# voltage-selector-and-output.net
KiCad netlist of a schematic drawn in EAGLE
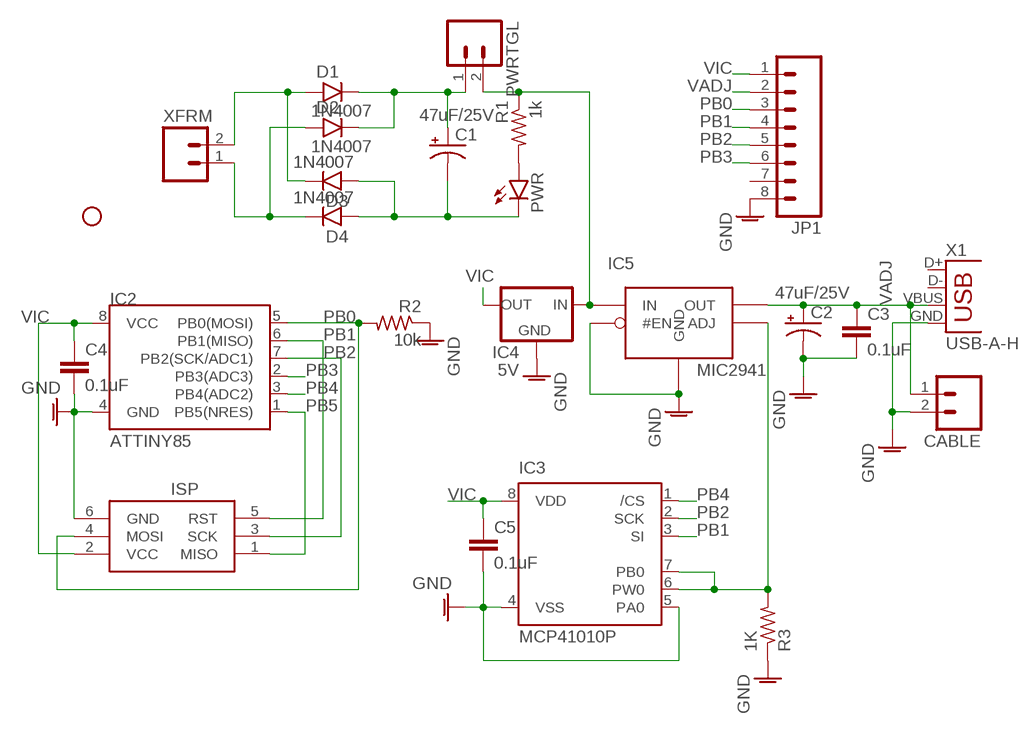
[diagram p0: schematic, sheet 1]

(export (version "E")
  (design (tool "Eeschema 10.0.6"))
  (components
    (comp (ref "C1")
      (value "47uF/25V")
      (footprint "eagle-import:E2,5-6")
      (libsource (lib "eagle-import") (part "CPOL-USE2.5-6"))
    )
    (comp (ref "C2")
      (value "47uF/25V")
      (footprint "eagle-import:E2,5-6")
      (libsource (lib "eagle-import") (part "CPOL-USE2.5-6"))
    )
    (comp (ref "C3")
      (value "0.1uF")
      (footprint "eagle-import:CAP-PTH-SMALL")
      (libsource (lib "eagle-import") (part "CAPPTH"))
    )
    (comp (ref "C4")
      (value "0.1uF")
      (footprint "eagle-import:CAP-PTH-SMALL")
      (libsource (lib "eagle-import") (part "CAPPTH"))
    )
    (comp (ref "C5")
      (value "0.1uF")
      (footprint "eagle-import:CAP-PTH-SMALL")
      (libsource (lib "eagle-import") (part "CAPPTH"))
    )
    (comp (ref "CABLE")
      (value "M02PTH")
      (footprint "eagle-import:1X02")
      (libsource (lib "eagle-import") (part "M02PTH"))
    )
    (comp (ref "D1")
      (value "1N4007")
      (footprint "eagle-import:DO41-3")
      (libsource (lib "eagle-import") (part "1N400X.3"))
    )
    (comp (ref "D2")
      (value "1N4007")
      (footprint "eagle-import:DO41-3")
      (libsource (lib "eagle-import") (part "1N400X.3"))
    )
    (comp (ref "D3")
      (value "1N4007")
      (footprint "eagle-import:DO41-3")
      (libsource (lib "eagle-import") (part "1N400X.3"))
    )
    (comp (ref "D4")
      (value "1N4007")
      (footprint "eagle-import:DO41-3")
      (libsource (lib "eagle-import") (part "1N400X.3"))
    )
    (comp (ref "IC2")
      (value "ATTINY85")
      (footprint "eagle-import:DIP08")
      (libsource (lib "eagle-import") (part "ATTINY13DIP"))
    )
    (comp (ref "IC3")
      (value "MCP41010P")
      (footprint "eagle-import:DIL8")
      (fields (field (name "MF") "MICROCHIP") (field (name "MPN") "MCP41010"))
      (libsource (lib "eagle-import") (part "MCP41010P"))
    )
    (comp (ref "IC4")
      (value "5V")
      (footprint "eagle-import:78XXS")
      (libsource (lib "eagle-import") (part "78XXS"))
    )
    (comp (ref "IC5")
      (value "MIC2941")
      (footprint "eagle-import:TO220-5")
      (libsource (lib "eagle-import") (part "MIC2941"))
    )
    (comp (ref "ISP")
      (value "AVRISP-6")
      (footprint "eagle-import:AVRISP")
      (libsource (lib "eagle-import") (part "AVRISP-6"))
    )
    (comp (ref "JP1")
      (value "M081X08")
      (footprint "eagle-import:1X08")
      (libsource (lib "eagle-import") (part "M081X08"))
    )
    (comp (ref "PWR")
      (value "LED-3MM-NO_SILK")
      (footprint "eagle-import:LED3MM-NS")
      (libsource (lib "eagle-import") (part "LED-3MM-NO_SILK"))
    )
    (comp (ref "PWRTGL")
      (value "M02PTH")
      (footprint "eagle-import:1X02")
      (libsource (lib "eagle-import") (part "M02PTH"))
    )
    (comp (ref "R1")
      (value "1k")
      (footprint "eagle-import:0207_5V")
      (libsource (lib "eagle-import") (part "R-US_0207/5V"))
    )
    (comp (ref "R2")
      (value "10k")
      (footprint "eagle-import:0207_5V")
      (libsource (lib "eagle-import") (part "R-US_0207/5V"))
    )
    (comp (ref "R3")
      (value "1K")
      (footprint "eagle-import:0207_5V")
      (libsource (lib "eagle-import") (part "R-US_0207/5V"))
    )
    (comp (ref "STANDOFF1")
      (value "STAND-OFF")
      (footprint "eagle-import:STAND-OFF")
      (libsource (lib "eagle-import") (part "STAND-OFF"))
    )
    (comp (ref "X1")
      (value "USB-A-H")
      (footprint "eagle-import:USB-A-H")
      (libsource (lib "eagle-import") (part "USB-A-H"))
    )
    (comp (ref "XFRM")
      (value "M02PTH")
      (footprint "eagle-import:1X02")
      (libsource (lib "eagle-import") (part "M02PTH"))
    )
  )
  (nets
    (net (code "1") (name "AGND") (class "Default")
      (node (ref "C2") (pin "-") (pinfunction "-_-") (pintype "passive"))
      (node (ref "C3") (pin "2") (pinfunction "2_2") (pintype "passive"))
      (node (ref "C4") (pin "2") (pinfunction "2_2") (pintype "passive"))
      (node (ref "C5") (pin "2") (pinfunction "2_2") (pintype "passive"))
      (node (ref "CABLE") (pin "2") (pinfunction "2_2") (pintype "passive"))
      (node (ref "IC2") (pin "4") (pinfunction "GND_4") (pintype "bidirectional"))
      (node (ref "IC3") (pin "4") (pinfunction "VSS_4") (pintype "power_in"))
      (node (ref "IC3") (pin "5") (pinfunction "PA0_5") (pintype "bidirectional"))
      (node (ref "IC4") (pin "GND") (pinfunction "GND_GND") (pintype "input"))
      (node (ref "IC5") (pin "2") (pinfunction "#EN_2") (pintype "input"))
      (node (ref "IC5") (pin "3") (pinfunction "GND_3") (pintype "input"))
      (node (ref "ISP") (pin "6") (pinfunction "GND_6") (pintype "power_in"))
      (node (ref "JP1") (pin "8") (pinfunction "8_8") (pintype "passive"))
      (node (ref "R2") (pin "1") (pinfunction "1_1") (pintype "passive"))
      (node (ref "R3") (pin "1") (pinfunction "1_1") (pintype "passive"))
      (node (ref "X1") (pin "GND") (pinfunction "GND_GND") (pintype "bidirectional"))
    )
    (net (code "2") (name "Net-(C1-Pad+)") (class "Default")
      (node (ref "C1") (pin "+") (pinfunction "+_+") (pintype "passive"))
      (node (ref "D1") (pin "C") (pinfunction "C_C") (pintype "passive"))
      (node (ref "D2") (pin "C") (pinfunction "C_C") (pintype "passive"))
      (node (ref "PWRTGL") (pin "1") (pinfunction "1_1") (pintype "passive"))
    )
    (net (code "3") (name "Net-(D1-PadA)") (class "Default")
      (node (ref "D1") (pin "A") (pinfunction "A_A") (pintype "passive"))
      (node (ref "D3") (pin "C") (pinfunction "C_C") (pintype "passive"))
      (node (ref "XFRM") (pin "2") (pinfunction "2_2") (pintype "passive"))
    )
    (net (code "4") (name "Net-(D2-PadA)") (class "Default")
      (node (ref "D2") (pin "A") (pinfunction "A_A") (pintype "passive"))
      (node (ref "D4") (pin "C") (pinfunction "C_C") (pintype "passive"))
      (node (ref "XFRM") (pin "1") (pinfunction "1_1") (pintype "passive"))
    )
    (net (code "5") (name "Net-(IC3-PB0)") (class "Default")
      (node (ref "IC3") (pin "6") (pinfunction "PW0_6") (pintype "bidirectional"))
      (node (ref "IC3") (pin "7") (pinfunction "PB0_7") (pintype "bidirectional"))
      (node (ref "IC5") (pin "1") (pinfunction "ADJ_1") (pintype "input"))
      (node (ref "R3") (pin "2") (pinfunction "2_2") (pintype "passive"))
    )
    (net (code "6") (name "Net-(IC5-IN)") (class "Default")
      (node (ref "IC4") (pin "IN") (pinfunction "IN_IN") (pintype "input"))
      (node (ref "IC5") (pin "4") (pinfunction "IN_4") (pintype "input"))
      (node (ref "PWRTGL") (pin "2") (pinfunction "2_2") (pintype "passive"))
      (node (ref "R1") (pin "1") (pinfunction "1_1") (pintype "passive"))
    )
    (net (code "7") (name "Net-(PWR-C)") (class "Default")
      (node (ref "C1") (pin "-") (pinfunction "-_-") (pintype "passive"))
      (node (ref "D3") (pin "A") (pinfunction "A_A") (pintype "passive"))
      (node (ref "D4") (pin "A") (pinfunction "A_A") (pintype "passive"))
      (node (ref "PWR") (pin "K") (pinfunction "C_K") (pintype "passive"))
    )
    (net (code "8") (name "Net-(PWR-PadA)") (class "Default")
      (node (ref "PWR") (pin "A") (pinfunction "A_A") (pintype "passive"))
      (node (ref "R1") (pin "2") (pinfunction "2_2") (pintype "passive"))
    )
    (net (code "9") (name "PB0") (class "Default")
      (node (ref "IC2") (pin "5") (pinfunction "PB0(MOSI)_5") (pintype "bidirectional"))
      (node (ref "ISP") (pin "4") (pinfunction "MOSI_4") (pintype "output"))
      (node (ref "JP1") (pin "3") (pinfunction "3_3") (pintype "passive"))
      (node (ref "R2") (pin "2") (pinfunction "2_2") (pintype "passive"))
    )
    (net (code "10") (name "PB1") (class "Default")
      (node (ref "IC2") (pin "6") (pinfunction "PB1(MISO)_6") (pintype "bidirectional"))
      (node (ref "IC3") (pin "3") (pinfunction "SI_3") (pintype "input"))
      (node (ref "ISP") (pin "5") (pinfunction "RST_5") (pintype "output"))
      (node (ref "JP1") (pin "4") (pinfunction "4_4") (pintype "passive"))
    )
    (net (code "11") (name "PB2") (class "Default")
      (node (ref "IC2") (pin "7") (pinfunction "PB2(SCK/ADC1)_7") (pintype "bidirectional"))
      (node (ref "IC3") (pin "2") (pinfunction "SCK_2") (pintype "input"))
      (node (ref "ISP") (pin "3") (pinfunction "SCK_3") (pintype "output"))
      (node (ref "JP1") (pin "5") (pinfunction "5_5") (pintype "passive"))
    )
    (net (code "12") (name "PB3") (class "Default")
      (node (ref "IC2") (pin "2") (pinfunction "PB3(ADC3)_2") (pintype "bidirectional"))
      (node (ref "JP1") (pin "6") (pinfunction "6_6") (pintype "passive"))
    )
    (net (code "13") (name "PB4") (class "Default")
      (node (ref "IC2") (pin "3") (pinfunction "PB4(ADC2)_3") (pintype "bidirectional"))
      (node (ref "IC3") (pin "1") (pinfunction "/CS_1") (pintype "input"))
    )
    (net (code "14") (name "PB5") (class "Default")
      (node (ref "IC2") (pin "1") (pinfunction "PB5(NRES)_1") (pintype "bidirectional"))
      (node (ref "ISP") (pin "1") (pinfunction "MISO_1") (pintype "input"))
    )
    (net (code "15") (name "VADJ") (class "Default")
      (node (ref "C2") (pin "+") (pinfunction "+_+") (pintype "passive"))
      (node (ref "C3") (pin "1") (pinfunction "1_1") (pintype "passive"))
      (node (ref "CABLE") (pin "1") (pinfunction "1_1") (pintype "passive"))
      (node (ref "IC5") (pin "5") (pinfunction "OUT_5") (pintype "passive"))
      (node (ref "JP1") (pin "2") (pinfunction "2_2") (pintype "passive"))
      (node (ref "X1") (pin "VBUS") (pinfunction "VBUS_VBUS") (pintype "bidirectional"))
    )
    (net (code "16") (name "VIC") (class "Default")
      (node (ref "C4") (pin "1") (pinfunction "1_1") (pintype "passive"))
      (node (ref "C5") (pin "1") (pinfunction "1_1") (pintype "passive"))
      (node (ref "IC2") (pin "8") (pinfunction "VCC_8") (pintype "bidirectional"))
      (node (ref "IC3") (pin "8") (pinfunction "VDD_8") (pintype "power_in"))
      (node (ref "IC4") (pin "OUT") (pinfunction "OUT_OUT") (pintype "passive"))
      (node (ref "ISP") (pin "2") (pinfunction "VCC_2") (pintype "power_in"))
      (node (ref "JP1") (pin "1") (pinfunction "1_1") (pintype "passive"))
    )
    (net (code "17") (name "unconnected-(JP1-Pad7)") (class "Default")
      (node (ref "JP1") (pin "7") (pinfunction "7_7") (pintype "passive"))
    )
    (net (code "18") (name "unconnected-(X1-PadD+)") (class "Default")
      (node (ref "X1") (pin "D+") (pinfunction "D+_D+") (pintype "bidirectional"))
    )
    (net (code "19") (name "unconnected-(X1-PadD-)") (class "Default")
      (node (ref "X1") (pin "D-") (pinfunction "D-_D-") (pintype "bidirectional"))
    )
  )
)
